# main.net
KiCad netlist of a schematic drawn in EAGLE
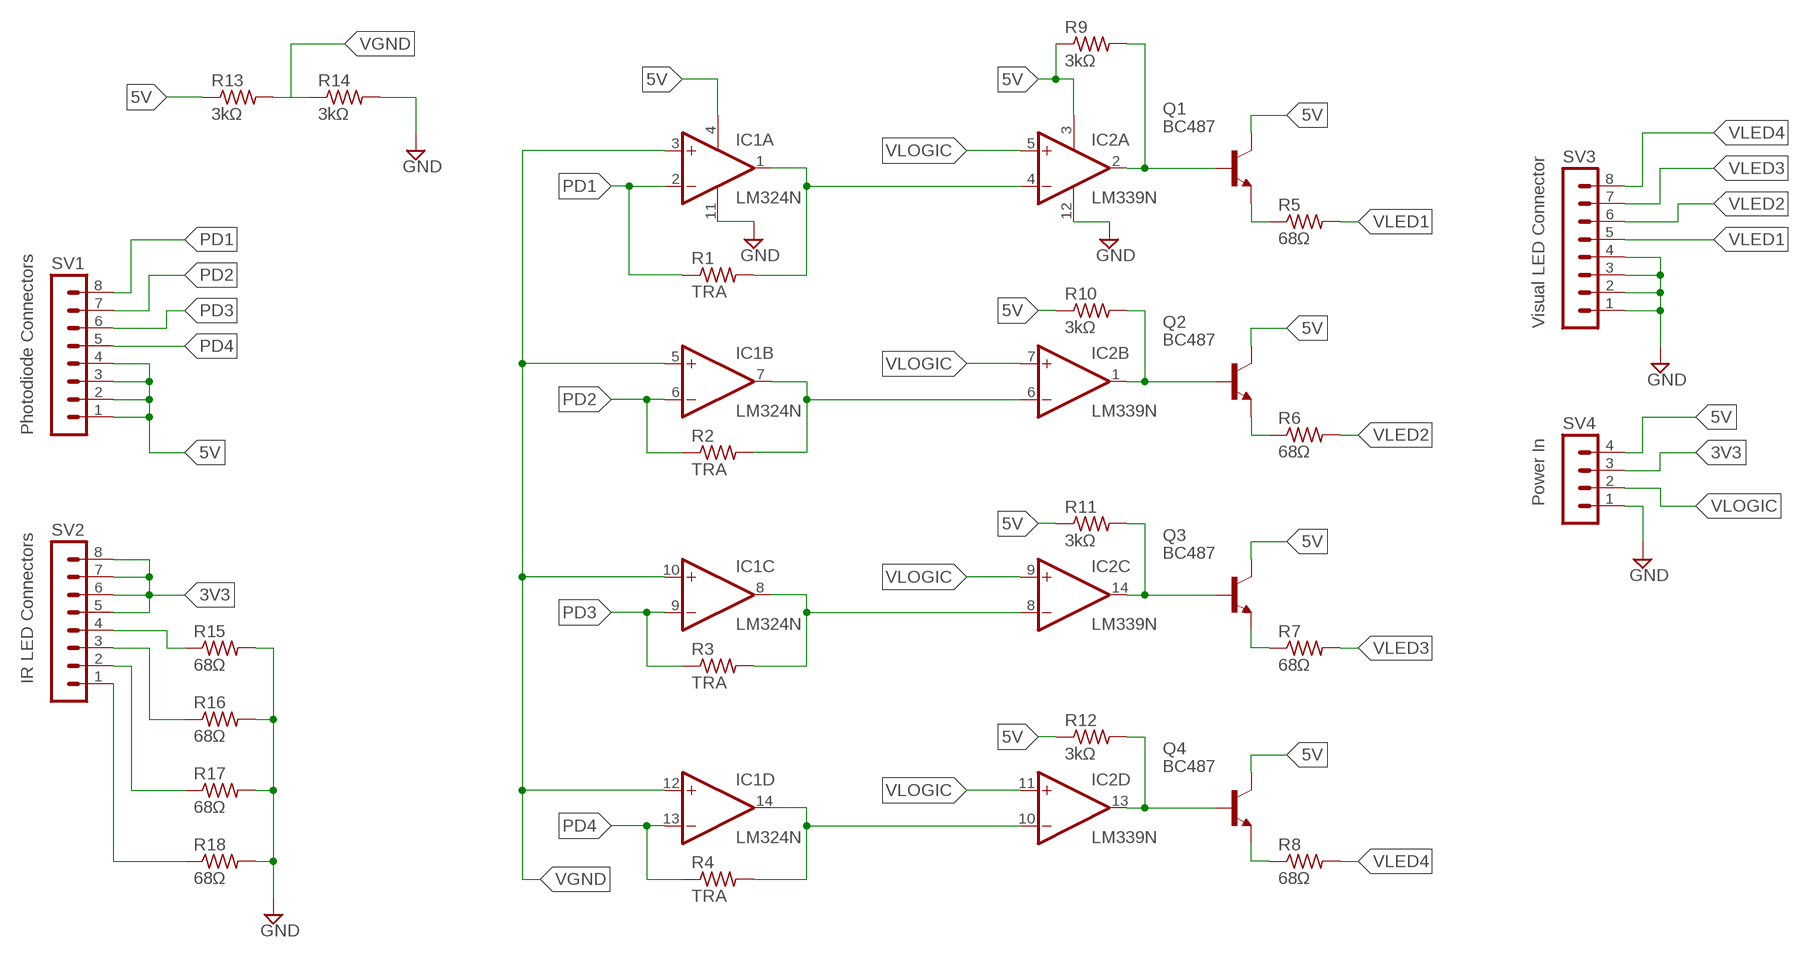
[diagram p0: schematic, sheet 1]

(export (version "E")
  (design (tool "Eeschema 10.0.6"))
  (components
    (comp (ref "IC1")
      (value "LM324N")
      (footprint "eagle-import:DIL14")
      (libsource (lib "eagle-import") (part "LM324N"))
    )
    (comp (ref "IC2")
      (value "LM339N")
      (footprint "eagle-import:DIL14")
      (libsource (lib "eagle-import") (part "LM339N"))
    )
    (comp (ref "Q1")
      (value "BC487")
      (footprint "eagle-import:TO92-EBC")
      (libsource (lib "eagle-import") (part "BC487"))
    )
    (comp (ref "Q2")
      (value "BC487")
      (footprint "eagle-import:TO92-EBC")
      (libsource (lib "eagle-import") (part "BC487"))
    )
    (comp (ref "Q3")
      (value "BC487")
      (footprint "eagle-import:TO92-EBC")
      (libsource (lib "eagle-import") (part "BC487"))
    )
    (comp (ref "Q4")
      (value "BC487")
      (footprint "eagle-import:TO92-EBC")
      (libsource (lib "eagle-import") (part "BC487"))
    )
    (comp (ref "R1")
      (value "TRA")
      (footprint "eagle-import:0204_7")
      (libsource (lib "eagle-import") (part "R-US_0204/7"))
    )
    (comp (ref "R2")
      (value "TRA")
      (footprint "eagle-import:0204_7")
      (libsource (lib "eagle-import") (part "R-US_0204/7"))
    )
    (comp (ref "R3")
      (value "TRA")
      (footprint "eagle-import:0204_7")
      (libsource (lib "eagle-import") (part "R-US_0204/7"))
    )
    (comp (ref "R4")
      (value "TRA")
      (footprint "eagle-import:0204_7")
      (libsource (lib "eagle-import") (part "R-US_0204/7"))
    )
    (comp (ref "R5")
      (value "68Ω")
      (footprint "eagle-import:0204_7")
      (libsource (lib "eagle-import") (part "R-US_0204/7"))
    )
    (comp (ref "R6")
      (value "68Ω")
      (footprint "eagle-import:0204_7")
      (libsource (lib "eagle-import") (part "R-US_0204/7"))
    )
    (comp (ref "R7")
      (value "68Ω")
      (footprint "eagle-import:0204_7")
      (libsource (lib "eagle-import") (part "R-US_0204/7"))
    )
    (comp (ref "R8")
      (value "68Ω")
      (footprint "eagle-import:0204_7")
      (libsource (lib "eagle-import") (part "R-US_0204/7"))
    )
    (comp (ref "R9")
      (value "3kΩ")
      (footprint "eagle-import:0204_7")
      (libsource (lib "eagle-import") (part "R-US_0204/7"))
    )
    (comp (ref "R10")
      (value "3kΩ")
      (footprint "eagle-import:0204_7")
      (libsource (lib "eagle-import") (part "R-US_0204/7"))
    )
    (comp (ref "R11")
      (value "3kΩ")
      (footprint "eagle-import:0204_7")
      (libsource (lib "eagle-import") (part "R-US_0204/7"))
    )
    (comp (ref "R12")
      (value "3kΩ")
      (footprint "eagle-import:0204_7")
      (libsource (lib "eagle-import") (part "R-US_0204/7"))
    )
    (comp (ref "R13")
      (value "3kΩ")
      (footprint "eagle-import:0204_7")
      (libsource (lib "eagle-import") (part "R-US_0204/7"))
    )
    (comp (ref "R14")
      (value "3kΩ")
      (footprint "eagle-import:0204_7")
      (libsource (lib "eagle-import") (part "R-US_0204/7"))
    )
    (comp (ref "R15")
      (value "68Ω")
      (footprint "eagle-import:0204_7")
      (libsource (lib "eagle-import") (part "R-US_0204/7"))
    )
    (comp (ref "R16")
      (value "68Ω")
      (footprint "eagle-import:0204_7")
      (libsource (lib "eagle-import") (part "R-US_0204/7"))
    )
    (comp (ref "R17")
      (value "68Ω")
      (footprint "eagle-import:0204_7")
      (libsource (lib "eagle-import") (part "R-US_0204/7"))
    )
    (comp (ref "R18")
      (value "68Ω")
      (footprint "eagle-import:0204_7")
      (libsource (lib "eagle-import") (part "R-US_0204/7"))
    )
    (comp (ref "SV1")
      (value "Photodiode Connectors")
      (footprint "eagle-import:MA08-1")
      (libsource (lib "eagle-import") (part "MA08-1"))
    )
    (comp (ref "SV2")
      (value "IR LED Connectors")
      (footprint "eagle-import:MA08-1")
      (libsource (lib "eagle-import") (part "MA08-1"))
    )
    (comp (ref "SV3")
      (value "Visual LED Connector")
      (footprint "eagle-import:MA08-1")
      (libsource (lib "eagle-import") (part "MA08-1"))
    )
    (comp (ref "SV4")
      (value "Power In")
      (footprint "eagle-import:MA04-1")
      (libsource (lib "eagle-import") (part "MA04-1"))
    )
  )
  (nets
    (net (code "1") (name "3V3") (class "Default")
      (node (ref "SV2") (pin "5") (pinfunction "5_5") (pintype "passive"))
      (node (ref "SV2") (pin "6") (pinfunction "6_6") (pintype "passive"))
      (node (ref "SV2") (pin "7") (pinfunction "7_7") (pintype "passive"))
      (node (ref "SV2") (pin "8") (pinfunction "8_8") (pintype "passive"))
      (node (ref "SV4") (pin "3") (pinfunction "3_3") (pintype "passive"))
    )
    (net (code "2") (name "5V") (class "Default")
      (node (ref "IC1") (pin "4") (pinfunction "V+_4") (pintype "power_in"))
      (node (ref "IC2") (pin "3") (pinfunction "V+_3") (pintype "power_in"))
      (node (ref "Q1") (pin "C") (pinfunction "C_C") (pintype "passive"))
      (node (ref "Q2") (pin "C") (pinfunction "C_C") (pintype "passive"))
      (node (ref "Q3") (pin "C") (pinfunction "C_C") (pintype "passive"))
      (node (ref "Q4") (pin "C") (pinfunction "C_C") (pintype "passive"))
      (node (ref "R10") (pin "1") (pinfunction "1_1") (pintype "passive"))
      (node (ref "R11") (pin "1") (pinfunction "1_1") (pintype "passive"))
      (node (ref "R12") (pin "1") (pinfunction "1_1") (pintype "passive"))
      (node (ref "R13") (pin "1") (pinfunction "1_1") (pintype "passive"))
      (node (ref "R9") (pin "1") (pinfunction "1_1") (pintype "passive"))
      (node (ref "SV1") (pin "1") (pinfunction "1_1") (pintype "passive"))
      (node (ref "SV1") (pin "2") (pinfunction "2_2") (pintype "passive"))
      (node (ref "SV1") (pin "3") (pinfunction "3_3") (pintype "passive"))
      (node (ref "SV1") (pin "4") (pinfunction "4_4") (pintype "passive"))
      (node (ref "SV4") (pin "4") (pinfunction "4_4") (pintype "passive"))
    )
    (net (code "3") (name "GND") (class "Default")
      (node (ref "IC1") (pin "11") (pinfunction "V-_11") (pintype "power_in"))
      (node (ref "IC2") (pin "12") (pinfunction "GND_12") (pintype "power_in"))
      (node (ref "R14") (pin "2") (pinfunction "2_2") (pintype "passive"))
      (node (ref "R15") (pin "2") (pinfunction "2_2") (pintype "passive"))
      (node (ref "R16") (pin "2") (pinfunction "2_2") (pintype "passive"))
      (node (ref "R17") (pin "2") (pinfunction "2_2") (pintype "passive"))
      (node (ref "R18") (pin "2") (pinfunction "2_2") (pintype "passive"))
      (node (ref "SV3") (pin "1") (pinfunction "1_1") (pintype "passive"))
      (node (ref "SV3") (pin "2") (pinfunction "2_2") (pintype "passive"))
      (node (ref "SV3") (pin "3") (pinfunction "3_3") (pintype "passive"))
      (node (ref "SV3") (pin "4") (pinfunction "4_4") (pintype "passive"))
      (node (ref "SV4") (pin "1") (pinfunction "1_1") (pintype "passive"))
    )
    (net (code "4") (name "Net-(IC1A-OUT)") (class "Default")
      (node (ref "IC1") (pin "1") (pinfunction "OUT_1") (pintype "output"))
      (node (ref "IC2") (pin "4") (pinfunction "-IN_4") (pintype "input"))
      (node (ref "R1") (pin "2") (pinfunction "2_2") (pintype "passive"))
    )
    (net (code "5") (name "Net-(IC1B-OUT)") (class "Default")
      (node (ref "IC1") (pin "7") (pinfunction "OUT_7") (pintype "output"))
      (node (ref "IC2") (pin "6") (pinfunction "-IN_6") (pintype "input"))
      (node (ref "R2") (pin "2") (pinfunction "2_2") (pintype "passive"))
    )
    (net (code "6") (name "Net-(IC1D-OUT)") (class "Default")
      (node (ref "IC1") (pin "14") (pinfunction "OUT_14") (pintype "output"))
      (node (ref "IC2") (pin "10") (pinfunction "-IN_10") (pintype "input"))
      (node (ref "R4") (pin "2") (pinfunction "2_2") (pintype "passive"))
    )
    (net (code "7") (name "Net-(IC2A-OUT)") (class "Default")
      (node (ref "IC2") (pin "2") (pinfunction "OUT_2") (pintype "open_collector"))
      (node (ref "Q1") (pin "B") (pinfunction "B_B") (pintype "passive"))
      (node (ref "R9") (pin "2") (pinfunction "2_2") (pintype "passive"))
    )
    (net (code "8") (name "Net-(IC2B-OUT)") (class "Default")
      (node (ref "IC2") (pin "1") (pinfunction "OUT_1") (pintype "open_collector"))
      (node (ref "Q2") (pin "B") (pinfunction "B_B") (pintype "passive"))
      (node (ref "R10") (pin "2") (pinfunction "2_2") (pintype "passive"))
    )
    (net (code "9") (name "Net-(IC2C-OUT)") (class "Default")
      (node (ref "IC2") (pin "14") (pinfunction "OUT_14") (pintype "open_collector"))
      (node (ref "Q3") (pin "B") (pinfunction "B_B") (pintype "passive"))
      (node (ref "R11") (pin "2") (pinfunction "2_2") (pintype "passive"))
    )
    (net (code "10") (name "Net-(IC2D-OUT)") (class "Default")
      (node (ref "IC2") (pin "13") (pinfunction "OUT_13") (pintype "open_collector"))
      (node (ref "Q4") (pin "B") (pinfunction "B_B") (pintype "passive"))
      (node (ref "R12") (pin "2") (pinfunction "2_2") (pintype "passive"))
    )
    (net (code "11") (name "Net-(Q1-PadE)") (class "Default")
      (node (ref "Q1") (pin "E") (pinfunction "E_E") (pintype "passive"))
      (node (ref "R5") (pin "1") (pinfunction "1_1") (pintype "passive"))
    )
    (net (code "12") (name "Net-(Q2-PadE)") (class "Default")
      (node (ref "Q2") (pin "E") (pinfunction "E_E") (pintype "passive"))
      (node (ref "R6") (pin "1") (pinfunction "1_1") (pintype "passive"))
    )
    (net (code "13") (name "Net-(Q3-PadE)") (class "Default")
      (node (ref "Q3") (pin "E") (pinfunction "E_E") (pintype "passive"))
      (node (ref "R7") (pin "1") (pinfunction "1_1") (pintype "passive"))
    )
    (net (code "14") (name "Net-(Q4-PadE)") (class "Default")
      (node (ref "Q4") (pin "E") (pinfunction "E_E") (pintype "passive"))
      (node (ref "R8") (pin "1") (pinfunction "1_1") (pintype "passive"))
    )
    (net (code "15") (name "Net-(R15-Pad1)") (class "Default")
      (node (ref "R15") (pin "1") (pinfunction "1_1") (pintype "passive"))
      (node (ref "SV2") (pin "4") (pinfunction "4_4") (pintype "passive"))
    )
    (net (code "16") (name "Net-(R16-Pad1)") (class "Default")
      (node (ref "R16") (pin "1") (pinfunction "1_1") (pintype "passive"))
      (node (ref "SV2") (pin "3") (pinfunction "3_3") (pintype "passive"))
    )
    (net (code "17") (name "Net-(R17-Pad1)") (class "Default")
      (node (ref "R17") (pin "1") (pinfunction "1_1") (pintype "passive"))
      (node (ref "SV2") (pin "2") (pinfunction "2_2") (pintype "passive"))
    )
    (net (code "18") (name "Net-(R18-Pad1)") (class "Default")
      (node (ref "R18") (pin "1") (pinfunction "1_1") (pintype "passive"))
      (node (ref "SV2") (pin "1") (pinfunction "1_1") (pintype "passive"))
    )
    (net (code "19") (name "PD1") (class "Default")
      (node (ref "IC1") (pin "2") (pinfunction "-IN_2") (pintype "input"))
      (node (ref "R1") (pin "1") (pinfunction "1_1") (pintype "passive"))
      (node (ref "SV1") (pin "8") (pinfunction "8_8") (pintype "passive"))
    )
    (net (code "20") (name "PD2") (class "Default")
      (node (ref "IC1") (pin "6") (pinfunction "-IN_6") (pintype "input"))
      (node (ref "R2") (pin "1") (pinfunction "1_1") (pintype "passive"))
      (node (ref "SV1") (pin "7") (pinfunction "7_7") (pintype "passive"))
    )
    (net (code "21") (name "PD3") (class "Default")
      (node (ref "IC1") (pin "9") (pinfunction "-IN_9") (pintype "input"))
      (node (ref "R3") (pin "1") (pinfunction "1_1") (pintype "passive"))
      (node (ref "SV1") (pin "6") (pinfunction "6_6") (pintype "passive"))
    )
    (net (code "22") (name "PD4") (class "Default")
      (node (ref "IC1") (pin "13") (pinfunction "-IN_13") (pintype "input"))
      (node (ref "R4") (pin "1") (pinfunction "1_1") (pintype "passive"))
      (node (ref "SV1") (pin "5") (pinfunction "5_5") (pintype "passive"))
    )
    (net (code "23") (name "VGND") (class "Default")
      (node (ref "IC1") (pin "10") (pinfunction "+IN_10") (pintype "input"))
      (node (ref "IC1") (pin "12") (pinfunction "+IN_12") (pintype "input"))
      (node (ref "IC1") (pin "3") (pinfunction "+IN_3") (pintype "input"))
      (node (ref "IC1") (pin "5") (pinfunction "+IN_5") (pintype "input"))
      (node (ref "R13") (pin "2") (pinfunction "2_2") (pintype "passive"))
      (node (ref "R14") (pin "1") (pinfunction "1_1") (pintype "passive"))
    )
    (net (code "24") (name "VLED1") (class "Default")
      (node (ref "R5") (pin "2") (pinfunction "2_2") (pintype "passive"))
      (node (ref "SV3") (pin "5") (pinfunction "5_5") (pintype "passive"))
    )
    (net (code "25") (name "VLED2") (class "Default")
      (node (ref "R6") (pin "2") (pinfunction "2_2") (pintype "passive"))
      (node (ref "SV3") (pin "6") (pinfunction "6_6") (pintype "passive"))
    )
    (net (code "26") (name "VLED3") (class "Default")
      (node (ref "R7") (pin "2") (pinfunction "2_2") (pintype "passive"))
      (node (ref "SV3") (pin "7") (pinfunction "7_7") (pintype "passive"))
    )
    (net (code "27") (name "VLED4") (class "Default")
      (node (ref "R8") (pin "2") (pinfunction "2_2") (pintype "passive"))
      (node (ref "SV3") (pin "8") (pinfunction "8_8") (pintype "passive"))
    )
    (net (code "28") (name "VLOGIC") (class "Default")
      (node (ref "IC1") (pin "8") (pinfunction "OUT_8") (pintype "output"))
      (node (ref "IC2") (pin "11") (pinfunction "+IN_11") (pintype "input"))
      (node (ref "IC2") (pin "5") (pinfunction "+IN_5") (pintype "input"))
      (node (ref "IC2") (pin "7") (pinfunction "+IN_7") (pintype "input"))
      (node (ref "IC2") (pin "8") (pinfunction "-IN_8") (pintype "input"))
      (node (ref "IC2") (pin "9") (pinfunction "+IN_9") (pintype "input"))
      (node (ref "R3") (pin "2") (pinfunction "2_2") (pintype "passive"))
      (node (ref "SV4") (pin "2") (pinfunction "2_2") (pintype "passive"))
    )
  )
)
